# LB_BIT_i37_mix_v03_3_5.net
KiCad netlist of a schematic drawn in EAGLE
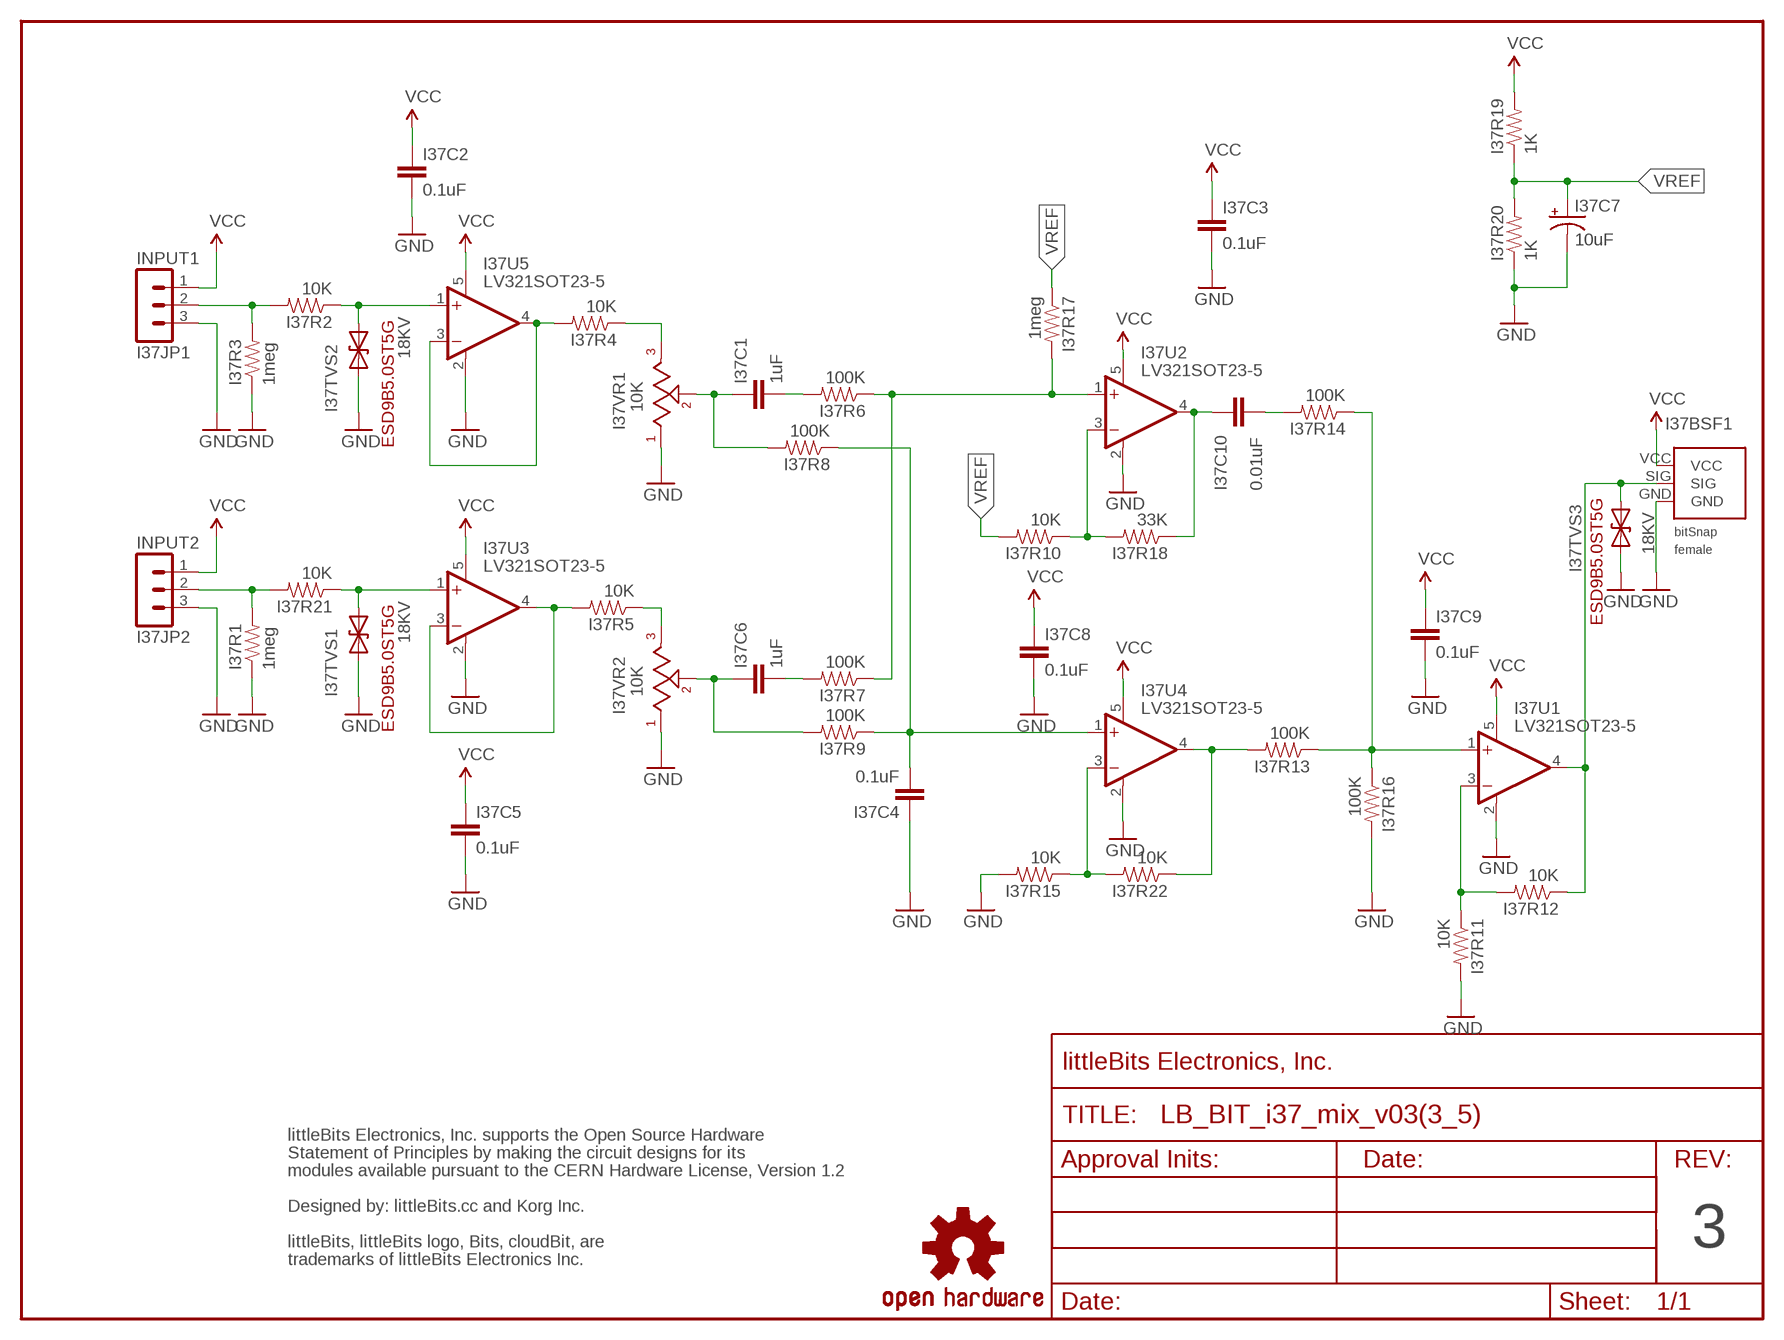
[diagram p0: schematic, sheet 1]

(export (version "E")
  (design (tool "Eeschema 10.0.6"))
  (components
    (comp (ref "I37BSF1")
      (value "BITSNAP_V03_FEMALE")
      (footprint "eagle-import:BITSNAP_V03_FEMALE")
      (libsource (lib "eagle-import") (part "BITSNAP_V03_FEMALE"))
    )
    (comp (ref "I37C1")
      (value "1uF")
      (footprint "eagle-import:CAP-0603")
      (libsource (lib "eagle-import") (part "CAPCAP-0603"))
    )
    (comp (ref "I37C2")
      (value "0.1uF")
      (footprint "eagle-import:CAP-0603")
      (libsource (lib "eagle-import") (part "CAPCAP-0603"))
    )
    (comp (ref "I37C3")
      (value "0.1uF")
      (footprint "eagle-import:CAP-0603")
      (libsource (lib "eagle-import") (part "CAPCAP-0603"))
    )
    (comp (ref "I37C4")
      (value "0.1uF")
      (footprint "eagle-import:CAP-0603")
      (libsource (lib "eagle-import") (part "CAPCAP-0603"))
    )
    (comp (ref "I37C5")
      (value "0.1uF")
      (footprint "eagle-import:CAP-0603")
      (libsource (lib "eagle-import") (part "CAPCAP-0603"))
    )
    (comp (ref "I37C6")
      (value "1uF")
      (footprint "eagle-import:CAP-0603")
      (libsource (lib "eagle-import") (part "CAPCAP-0603"))
    )
    (comp (ref "I37C7")
      (value "10uF")
      (footprint "eagle-import:EIA3216")
      (libsource (lib "eagle-import") (part "CAP_POL3216"))
    )
    (comp (ref "I37C8")
      (value "0.1uF")
      (footprint "eagle-import:CAP-0603")
      (libsource (lib "eagle-import") (part "CAPCAP-0603"))
    )
    (comp (ref "I37C9")
      (value "0.1uF")
      (footprint "eagle-import:CAP-0603")
      (libsource (lib "eagle-import") (part "CAPCAP-0603"))
    )
    (comp (ref "I37C10")
      (value "0.01uF")
      (footprint "eagle-import:CAP-0603")
      (libsource (lib "eagle-import") (part "CAPCAP-0603"))
    )
    (comp (ref "I37JP1")
      (value "INPUT1")
      (footprint "eagle-import:1X03-1MM-RA")
      (libsource (lib "eagle-import") (part "MA03-1SMD"))
    )
    (comp (ref "I37JP2")
      (value "INPUT2")
      (footprint "eagle-import:1X03-1MM-RA")
      (libsource (lib "eagle-import") (part "MA03-1SMD"))
    )
    (comp (ref "I37R1")
      (value "1meg")
      (footprint "eagle-import:RES-0603")
      (libsource (lib "eagle-import") (part "RESISTOR0603"))
    )
    (comp (ref "I37R2")
      (value "10K")
      (footprint "eagle-import:RES-0603")
      (libsource (lib "eagle-import") (part "RESISTOR0603"))
    )
    (comp (ref "I37R3")
      (value "1meg")
      (footprint "eagle-import:RES-0603")
      (libsource (lib "eagle-import") (part "RESISTOR0603"))
    )
    (comp (ref "I37R4")
      (value "10K")
      (footprint "eagle-import:RES-0603")
      (libsource (lib "eagle-import") (part "RESISTOR0603"))
    )
    (comp (ref "I37R5")
      (value "10K")
      (footprint "eagle-import:RES-0603")
      (libsource (lib "eagle-import") (part "RESISTOR0603"))
    )
    (comp (ref "I37R6")
      (value "100K")
      (footprint "eagle-import:RES-0603")
      (libsource (lib "eagle-import") (part "RESISTOR0603"))
    )
    (comp (ref "I37R7")
      (value "100K")
      (footprint "eagle-import:RES-0603")
      (libsource (lib "eagle-import") (part "RESISTOR0603"))
    )
    (comp (ref "I37R8")
      (value "100K")
      (footprint "eagle-import:RES-0603")
      (libsource (lib "eagle-import") (part "RESISTOR0603"))
    )
    (comp (ref "I37R9")
      (value "100K")
      (footprint "eagle-import:RES-0603")
      (libsource (lib "eagle-import") (part "RESISTOR0603"))
    )
    (comp (ref "I37R10")
      (value "10K")
      (footprint "eagle-import:RES-0603")
      (libsource (lib "eagle-import") (part "RESISTOR0603"))
    )
    (comp (ref "I37R11")
      (value "10K")
      (footprint "eagle-import:RES-0603")
      (libsource (lib "eagle-import") (part "RESISTOR0603"))
    )
    (comp (ref "I37R12")
      (value "10K")
      (footprint "eagle-import:RES-0603")
      (libsource (lib "eagle-import") (part "RESISTOR0603"))
    )
    (comp (ref "I37R13")
      (value "100K")
      (footprint "eagle-import:RES-0603")
      (libsource (lib "eagle-import") (part "RESISTOR0603"))
    )
    (comp (ref "I37R14")
      (value "100K")
      (footprint "eagle-import:RES-0603")
      (libsource (lib "eagle-import") (part "RESISTOR0603"))
    )
    (comp (ref "I37R15")
      (value "10K")
      (footprint "eagle-import:RES-0603")
      (libsource (lib "eagle-import") (part "RESISTOR0603"))
    )
    (comp (ref "I37R16")
      (value "100K")
      (footprint "eagle-import:RES-0603")
      (libsource (lib "eagle-import") (part "RESISTOR0603"))
    )
    (comp (ref "I37R17")
      (value "1meg")
      (footprint "eagle-import:RES-0603")
      (libsource (lib "eagle-import") (part "RESISTOR0603"))
    )
    (comp (ref "I37R18")
      (value "33K")
      (footprint "eagle-import:RES-0603")
      (libsource (lib "eagle-import") (part "RESISTOR0603"))
    )
    (comp (ref "I37R19")
      (value "1K")
      (footprint "eagle-import:RES-0603")
      (libsource (lib "eagle-import") (part "RESISTOR0603"))
    )
    (comp (ref "I37R20")
      (value "1K")
      (footprint "eagle-import:RES-0603")
      (libsource (lib "eagle-import") (part "RESISTOR0603"))
    )
    (comp (ref "I37R21")
      (value "10K")
      (footprint "eagle-import:RES-0603")
      (libsource (lib "eagle-import") (part "RESISTOR0603"))
    )
    (comp (ref "I37R22")
      (value "10K")
      (footprint "eagle-import:RES-0603")
      (libsource (lib "eagle-import") (part "RESISTOR0603"))
    )
    (comp (ref "I37TVS1")
      (value "18KV")
      (footprint "eagle-import:SOD-923")
      (fields (field (name "MPN") "ESD9B5.0ST5G"))
      (libsource (lib "eagle-import") (part "DIODE-TVSSOD-923"))
    )
    (comp (ref "I37TVS2")
      (value "18KV")
      (footprint "eagle-import:SOD-923")
      (fields (field (name "MPN") "ESD9B5.0ST5G"))
      (libsource (lib "eagle-import") (part "DIODE-TVSSOD-923"))
    )
    (comp (ref "I37TVS3")
      (value "18KV")
      (footprint "eagle-import:SOD-923")
      (fields (field (name "MPN") "ESD9B5.0ST5G"))
      (libsource (lib "eagle-import") (part "DIODE-TVSSOD-923"))
    )
    (comp (ref "I37U1")
      (value "LV321SOT23-5")
      (footprint "eagle-import:SOT23-5")
      (libsource (lib "eagle-import") (part "LV321SOT23-5"))
    )
    (comp (ref "I37U2")
      (value "LV321SOT23-5")
      (footprint "eagle-import:SOT23-5")
      (libsource (lib "eagle-import") (part "LV321SOT23-5"))
    )
    (comp (ref "I37U3")
      (value "LV321SOT23-5")
      (footprint "eagle-import:SOT23-5")
      (libsource (lib "eagle-import") (part "LV321SOT23-5"))
    )
    (comp (ref "I37U4")
      (value "LV321SOT23-5")
      (footprint "eagle-import:SOT23-5")
      (libsource (lib "eagle-import") (part "LV321SOT23-5"))
    )
    (comp (ref "I37U5")
      (value "LV321SOT23-5")
      (footprint "eagle-import:SOT23-5")
      (libsource (lib "eagle-import") (part "LV321SOT23-5"))
    )
    (comp (ref "I37VR1")
      (value "10K")
      (footprint "eagle-import:ALPS_POT")
      (libsource (lib "eagle-import") (part "ALPS_POTTH"))
    )
    (comp (ref "I37VR2")
      (value "10K")
      (footprint "eagle-import:ALPS_POT")
      (libsource (lib "eagle-import") (part "ALPS_POTTH"))
    )
    (comp (ref "U$1")
      (value "OSHWCREDIT-KORG")
      (footprint "eagle-import:OSHWCREDIT-KORG")
      (libsource (lib "eagle-import") (part "OSHWCREDIT-KORG"))
    )
    (comp (ref "U$2")
      (value "FRAME-LETTER-OHWOHW")
      (footprint "eagle-import:FABDWG01-OHW")
      (libsource (lib "eagle-import") (part "FRAME-LETTER-OHWOHW"))
    )
    (comp (ref "U$19")
      (value "OSHW-LOGOL")
      (footprint "eagle-import:OSHW-LOGO-L")
      (libsource (lib "eagle-import") (part "OSHW-LOGOL"))
    )
  )
  (nets
    (net (code "1") (name "GND") (class "Default")
      (node (ref "I37BSF1") (pin "GND") (pinfunction "GND_GND") (pintype "bidirectional"))
      (node (ref "I37C2") (pin "2") (pinfunction "2_2") (pintype "passive"))
      (node (ref "I37C3") (pin "2") (pinfunction "2_2") (pintype "passive"))
      (node (ref "I37C4") (pin "1") (pinfunction "1_1") (pintype "passive"))
      (node (ref "I37C5") (pin "2") (pinfunction "2_2") (pintype "passive"))
      (node (ref "I37C7") (pin "-") (pinfunction "-_-") (pintype "passive"))
      (node (ref "I37C8") (pin "2") (pinfunction "2_2") (pintype "passive"))
      (node (ref "I37C9") (pin "2") (pinfunction "2_2") (pintype "passive"))
      (node (ref "I37JP1") (pin "3") (pinfunction "3_3") (pintype "passive"))
      (node (ref "I37JP2") (pin "3") (pinfunction "3_3") (pintype "passive"))
      (node (ref "I37R1") (pin "1") (pinfunction "1_1") (pintype "passive"))
      (node (ref "I37R11") (pin "2") (pinfunction "2_2") (pintype "passive"))
      (node (ref "I37R15") (pin "2") (pinfunction "2_2") (pintype "passive"))
      (node (ref "I37R16") (pin "2") (pinfunction "2_2") (pintype "passive"))
      (node (ref "I37R20") (pin "1") (pinfunction "1_1") (pintype "passive"))
      (node (ref "I37R3") (pin "1") (pinfunction "1_1") (pintype "passive"))
      (node (ref "I37TVS1") (pin "1") (pinfunction "A_1") (pintype "passive"))
      (node (ref "I37TVS2") (pin "1") (pinfunction "A_1") (pintype "passive"))
      (node (ref "I37TVS3") (pin "1") (pinfunction "A_1") (pintype "passive"))
      (node (ref "I37U1") (pin "2") (pinfunction "V-_2") (pintype "power_in"))
      (node (ref "I37U2") (pin "2") (pinfunction "V-_2") (pintype "power_in"))
      (node (ref "I37U3") (pin "2") (pinfunction "V-_2") (pintype "power_in"))
      (node (ref "I37U4") (pin "2") (pinfunction "V-_2") (pintype "power_in"))
      (node (ref "I37U5") (pin "2") (pinfunction "V-_2") (pintype "power_in"))
      (node (ref "I37VR1") (pin "1") (pinfunction "1_1") (pintype "passive"))
      (node (ref "I37VR2") (pin "1") (pinfunction "1_1") (pintype "passive"))
    )
    (net (code "2") (name "Net-(I37C1-Pad1)") (class "Default")
      (node (ref "I37C1") (pin "1") (pinfunction "1_1") (pintype "passive"))
      (node (ref "I37R8") (pin "2") (pinfunction "2_2") (pintype "passive"))
      (node (ref "I37VR1") (pin "2") (pinfunction "2_2") (pintype "passive"))
    )
    (net (code "3") (name "Net-(I37C1-Pad2)") (class "Default")
      (node (ref "I37C1") (pin "2") (pinfunction "2_2") (pintype "passive"))
      (node (ref "I37R6") (pin "2") (pinfunction "2_2") (pintype "passive"))
    )
    (net (code "4") (name "Net-(I37C6-Pad1)") (class "Default")
      (node (ref "I37C6") (pin "1") (pinfunction "1_1") (pintype "passive"))
      (node (ref "I37R9") (pin "2") (pinfunction "2_2") (pintype "passive"))
      (node (ref "I37VR2") (pin "2") (pinfunction "2_2") (pintype "passive"))
    )
    (net (code "5") (name "Net-(I37C6-Pad2)") (class "Default")
      (node (ref "I37C6") (pin "2") (pinfunction "2_2") (pintype "passive"))
      (node (ref "I37R7") (pin "2") (pinfunction "2_2") (pintype "passive"))
    )
    (net (code "6") (name "Net-(I37C10-Pad2)") (class "Default")
      (node (ref "I37C10") (pin "2") (pinfunction "2_2") (pintype "passive"))
      (node (ref "I37R14") (pin "2") (pinfunction "2_2") (pintype "passive"))
    )
    (net (code "7") (name "Net-(I37JP1-Pad2)") (class "Default")
      (node (ref "I37JP1") (pin "2") (pinfunction "2_2") (pintype "passive"))
      (node (ref "I37R2") (pin "2") (pinfunction "2_2") (pintype "passive"))
      (node (ref "I37R3") (pin "2") (pinfunction "2_2") (pintype "passive"))
    )
    (net (code "8") (name "Net-(I37JP2-Pad2)") (class "Default")
      (node (ref "I37JP2") (pin "2") (pinfunction "2_2") (pintype "passive"))
      (node (ref "I37R1") (pin "2") (pinfunction "2_2") (pintype "passive"))
      (node (ref "I37R21") (pin "2") (pinfunction "2_2") (pintype "passive"))
    )
    (net (code "9") (name "Net-(I37R4-Pad1)") (class "Default")
      (node (ref "I37R4") (pin "1") (pinfunction "1_1") (pintype "passive"))
      (node (ref "I37VR1") (pin "3") (pinfunction "3_3") (pintype "passive"))
    )
    (net (code "10") (name "Net-(I37R5-Pad1)") (class "Default")
      (node (ref "I37R5") (pin "1") (pinfunction "1_1") (pintype "passive"))
      (node (ref "I37VR2") (pin "3") (pinfunction "3_3") (pintype "passive"))
    )
    (net (code "11") (name "Net-(I37TVS1-C)") (class "Default")
      (node (ref "I37R21") (pin "1") (pinfunction "1_1") (pintype "passive"))
      (node (ref "I37TVS1") (pin "2") (pinfunction "C_2") (pintype "passive"))
      (node (ref "I37U3") (pin "1") (pinfunction "+IN_1") (pintype "input"))
    )
    (net (code "12") (name "Net-(I37TVS2-C)") (class "Default")
      (node (ref "I37R2") (pin "1") (pinfunction "1_1") (pintype "passive"))
      (node (ref "I37TVS2") (pin "2") (pinfunction "C_2") (pintype "passive"))
      (node (ref "I37U5") (pin "1") (pinfunction "+IN_1") (pintype "input"))
    )
    (net (code "13") (name "Net-(I37TVS3-C)") (class "Default")
      (node (ref "I37BSF1") (pin "SIG") (pinfunction "SIG_SIG") (pintype "bidirectional"))
      (node (ref "I37R12") (pin "1") (pinfunction "1_1") (pintype "passive"))
      (node (ref "I37TVS3") (pin "2") (pinfunction "C_2") (pintype "passive"))
      (node (ref "I37U1") (pin "4") (pinfunction "OUT_4") (pintype "output"))
    )
    (net (code "14") (name "Net-(I37U1-+IN)") (class "Default")
      (node (ref "I37R13") (pin "1") (pinfunction "1_1") (pintype "passive"))
      (node (ref "I37R14") (pin "1") (pinfunction "1_1") (pintype "passive"))
      (node (ref "I37R16") (pin "1") (pinfunction "1_1") (pintype "passive"))
      (node (ref "I37U1") (pin "1") (pinfunction "+IN_1") (pintype "input"))
    )
    (net (code "15") (name "Net-(I37U1--IN)") (class "Default")
      (node (ref "I37R11") (pin "1") (pinfunction "1_1") (pintype "passive"))
      (node (ref "I37R12") (pin "2") (pinfunction "2_2") (pintype "passive"))
      (node (ref "I37U1") (pin "3") (pinfunction "-IN_3") (pintype "input"))
    )
    (net (code "16") (name "Net-(I37U2-+IN)") (class "Default")
      (node (ref "I37R17") (pin "2") (pinfunction "2_2") (pintype "passive"))
      (node (ref "I37R6") (pin "1") (pinfunction "1_1") (pintype "passive"))
      (node (ref "I37R7") (pin "1") (pinfunction "1_1") (pintype "passive"))
      (node (ref "I37U2") (pin "1") (pinfunction "+IN_1") (pintype "input"))
    )
    (net (code "17") (name "Net-(I37U2--IN)") (class "Default")
      (node (ref "I37R10") (pin "1") (pinfunction "1_1") (pintype "passive"))
      (node (ref "I37R18") (pin "2") (pinfunction "2_2") (pintype "passive"))
      (node (ref "I37U2") (pin "3") (pinfunction "-IN_3") (pintype "input"))
    )
    (net (code "18") (name "Net-(I37U2-OUT)") (class "Default")
      (node (ref "I37C10") (pin "1") (pinfunction "1_1") (pintype "passive"))
      (node (ref "I37R18") (pin "1") (pinfunction "1_1") (pintype "passive"))
      (node (ref "I37U2") (pin "4") (pinfunction "OUT_4") (pintype "output"))
    )
    (net (code "19") (name "Net-(I37U3--IN)") (class "Default")
      (node (ref "I37R5") (pin "2") (pinfunction "2_2") (pintype "passive"))
      (node (ref "I37U3") (pin "3") (pinfunction "-IN_3") (pintype "input"))
      (node (ref "I37U3") (pin "4") (pinfunction "OUT_4") (pintype "output"))
    )
    (net (code "20") (name "Net-(I37U4-+IN)") (class "Default")
      (node (ref "I37C4") (pin "2") (pinfunction "2_2") (pintype "passive"))
      (node (ref "I37R8") (pin "1") (pinfunction "1_1") (pintype "passive"))
      (node (ref "I37R9") (pin "1") (pinfunction "1_1") (pintype "passive"))
      (node (ref "I37U4") (pin "1") (pinfunction "+IN_1") (pintype "input"))
    )
    (net (code "21") (name "Net-(I37U4--IN)") (class "Default")
      (node (ref "I37R15") (pin "1") (pinfunction "1_1") (pintype "passive"))
      (node (ref "I37R22") (pin "2") (pinfunction "2_2") (pintype "passive"))
      (node (ref "I37U4") (pin "3") (pinfunction "-IN_3") (pintype "input"))
    )
    (net (code "22") (name "Net-(I37U4-OUT)") (class "Default")
      (node (ref "I37R13") (pin "2") (pinfunction "2_2") (pintype "passive"))
      (node (ref "I37R22") (pin "1") (pinfunction "1_1") (pintype "passive"))
      (node (ref "I37U4") (pin "4") (pinfunction "OUT_4") (pintype "output"))
    )
    (net (code "23") (name "Net-(I37U5--IN)") (class "Default")
      (node (ref "I37R4") (pin "2") (pinfunction "2_2") (pintype "passive"))
      (node (ref "I37U5") (pin "3") (pinfunction "-IN_3") (pintype "input"))
      (node (ref "I37U5") (pin "4") (pinfunction "OUT_4") (pintype "output"))
    )
    (net (code "24") (name "VCC") (class "Default")
      (node (ref "I37BSF1") (pin "VCC") (pinfunction "VCC_VCC") (pintype "bidirectional"))
      (node (ref "I37C2") (pin "1") (pinfunction "1_1") (pintype "passive"))
      (node (ref "I37C3") (pin "1") (pinfunction "1_1") (pintype "passive"))
      (node (ref "I37C5") (pin "1") (pinfunction "1_1") (pintype "passive"))
      (node (ref "I37C8") (pin "1") (pinfunction "1_1") (pintype "passive"))
      (node (ref "I37C9") (pin "1") (pinfunction "1_1") (pintype "passive"))
      (node (ref "I37JP1") (pin "1") (pinfunction "1_1") (pintype "passive"))
      (node (ref "I37JP2") (pin "1") (pinfunction "1_1") (pintype "passive"))
      (node (ref "I37R19") (pin "2") (pinfunction "2_2") (pintype "passive"))
      (node (ref "I37U1") (pin "5") (pinfunction "V+_5") (pintype "power_in"))
      (node (ref "I37U2") (pin "5") (pinfunction "V+_5") (pintype "power_in"))
      (node (ref "I37U3") (pin "5") (pinfunction "V+_5") (pintype "power_in"))
      (node (ref "I37U4") (pin "5") (pinfunction "V+_5") (pintype "power_in"))
      (node (ref "I37U5") (pin "5") (pinfunction "V+_5") (pintype "power_in"))
    )
    (net (code "25") (name "VREF") (class "Default")
      (node (ref "I37C7") (pin "+") (pinfunction "+_+") (pintype "passive"))
      (node (ref "I37R10") (pin "2") (pinfunction "2_2") (pintype "passive"))
      (node (ref "I37R17") (pin "1") (pinfunction "1_1") (pintype "passive"))
      (node (ref "I37R19") (pin "1") (pinfunction "1_1") (pintype "passive"))
      (node (ref "I37R20") (pin "2") (pinfunction "2_2") (pintype "passive"))
    )
  )
)
